# A07_BUS_CONTROL.net
KiCad netlist of a schematic drawn in Altium Designer
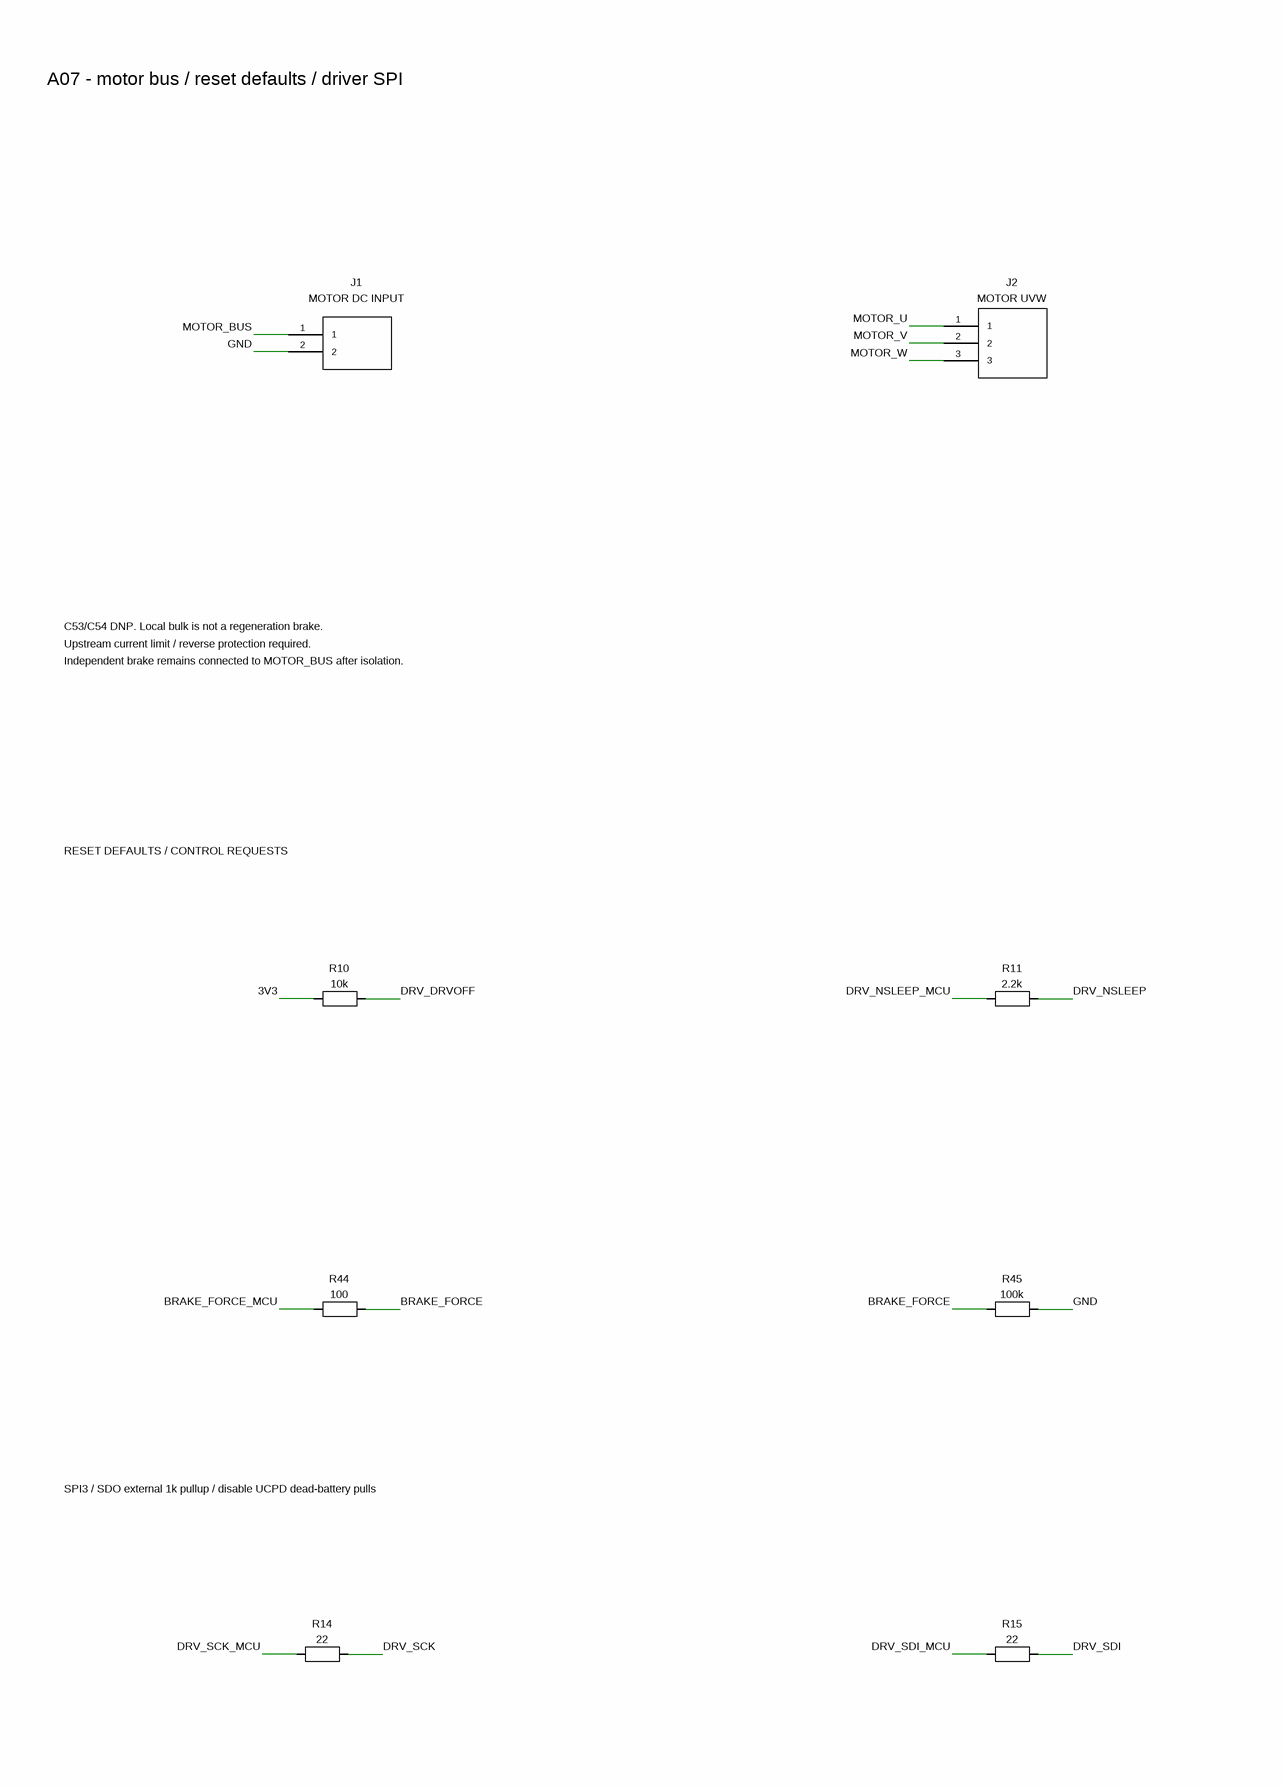
[diagram p0: A07_BUS_CONTROL.SchDoc, left]
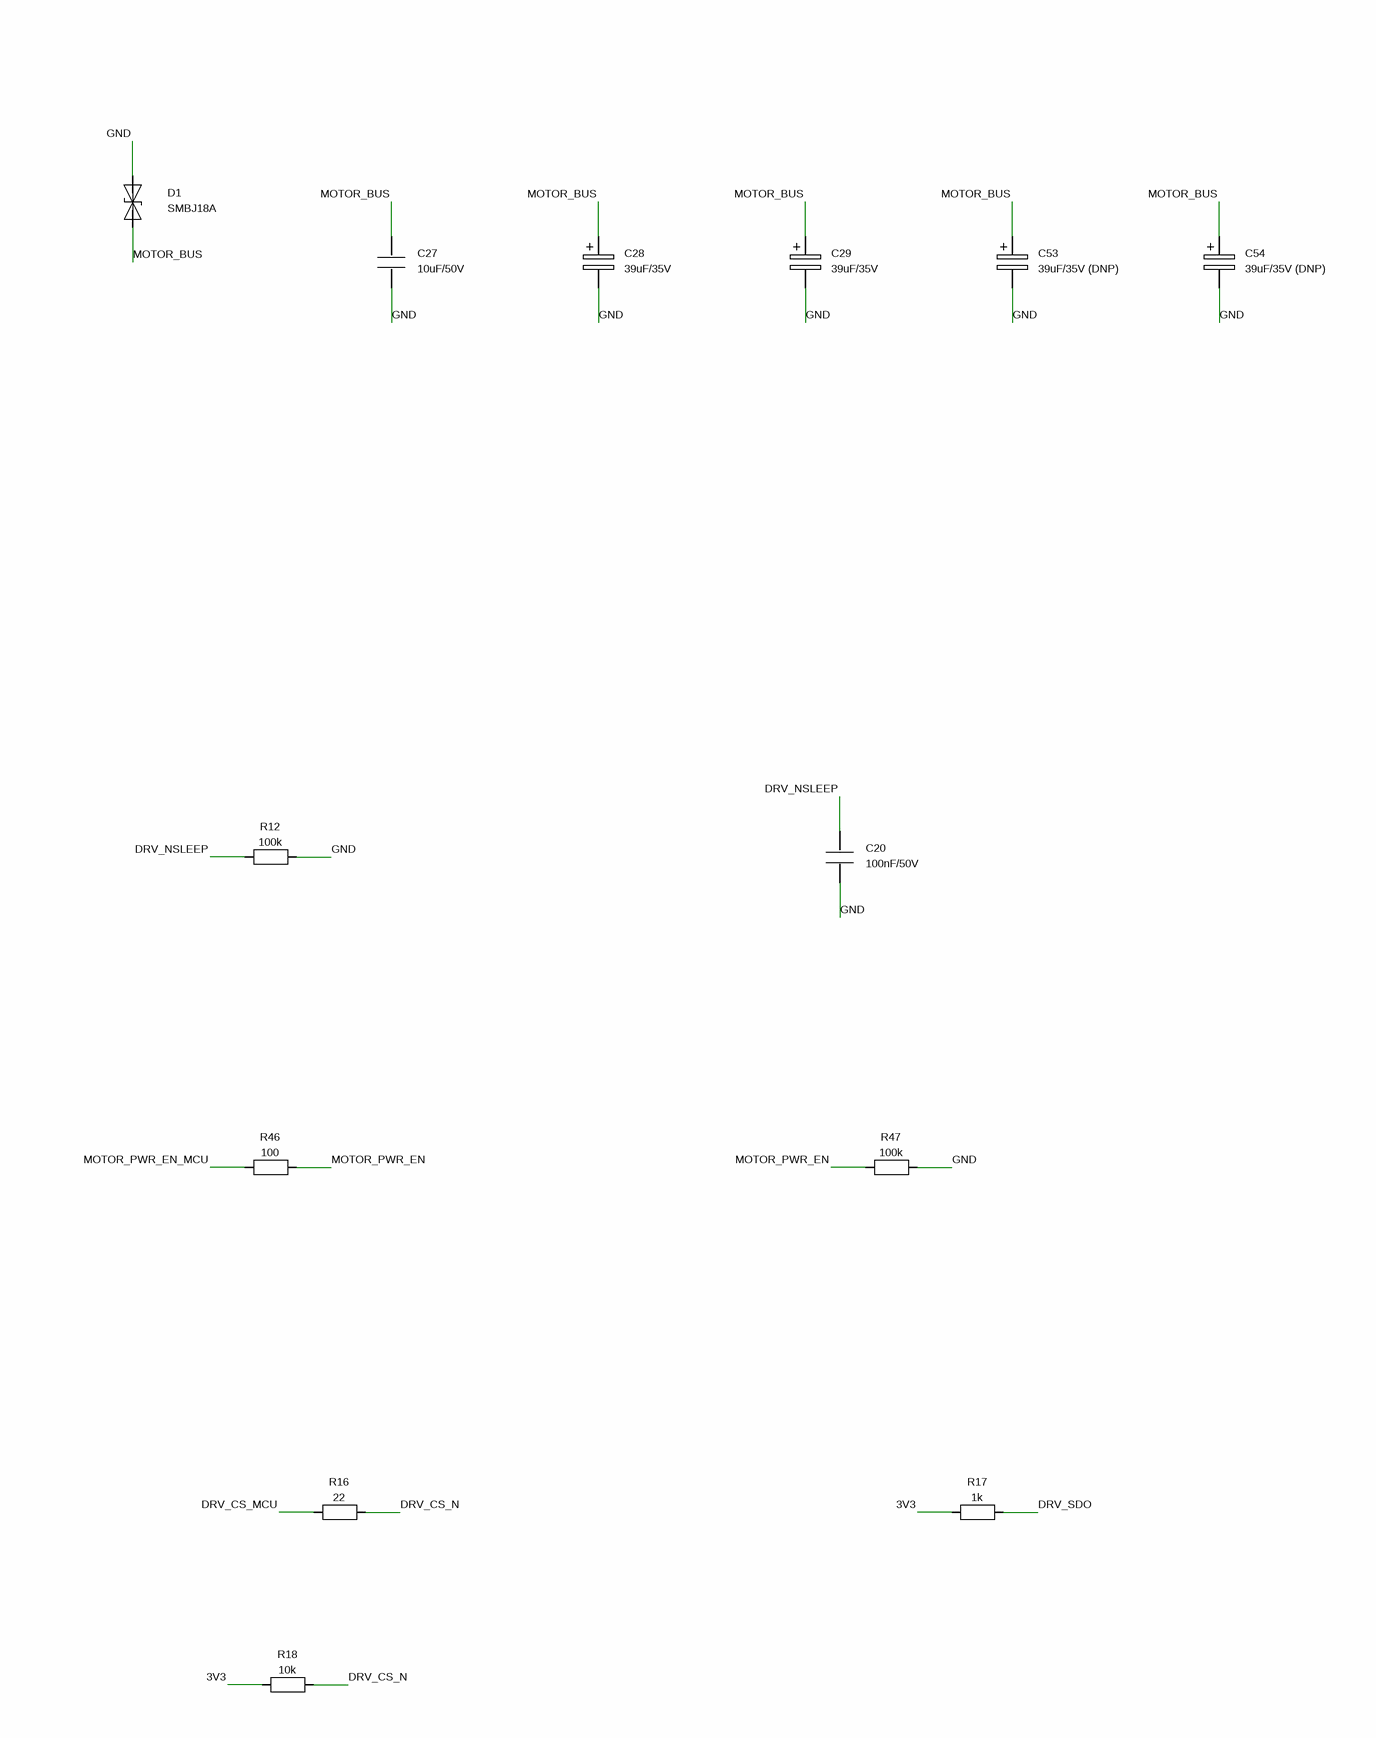
[diagram p1: A07_BUS_CONTROL.SchDoc, right]

(export (version "E")
  (design (tool "Eeschema 10.0.6"))
  (components
    (comp (ref "C20")
      (value "100nF/50V")
      (footprint "User_STM32F407_Ctrl:C0603_M")
      (description "电容")
      (fields (field (name "MPN") "CL10B104KB8NNNC"))
      (libsource (lib "altium-import") (part "root_0_C_"))
    )
    (comp (ref "C27")
      (value "10uF/50V")
      (footprint "User_SamacSys:CAPC3225X270N")
      (description "电容")
      (fields (field (name "MPN") "GRM32ER71H106KA12L"))
      (libsource (lib "altium-import") (part "root_0_C_"))
    )
    (comp (ref "C28")
      (value "39uF/35V")
      (footprint "User_SamacSys:16SVF270M")
      (description "电容")
      (fields (field (name "MPN") "35SVPF39M"))
      (libsource (lib "altium-import") (part "root_0_C_Polarized_"))
    )
    (comp (ref "C29")
      (value "39uF/35V")
      (footprint "User_SamacSys:16SVF270M")
      (description "电容")
      (fields (field (name "MPN") "35SVPF39M"))
      (libsource (lib "altium-import") (part "root_0_C_Polarized_"))
    )
    (comp (ref "C53")
      (value "39uF/35V (DNP)")
      (footprint "User_SamacSys:16SVF270M")
      (description "电容")
      (fields (field (name "MPN") "35SVPF39M"))
      (libsource (lib "altium-import") (part "root_0_C_Polarized_"))
    )
    (comp (ref "C54")
      (value "39uF/35V (DNP)")
      (footprint "User_SamacSys:16SVF270M")
      (description "电容")
      (fields (field (name "MPN") "35SVPF39M"))
      (libsource (lib "altium-import") (part "root_0_C_Polarized_"))
    )
    (comp (ref "D1")
      (value "SMBJ18A")
      (footprint "User_LCSC:C151256_DO-214AA")
      (description "母线瞬态TVS")
      (libsource (lib "altium-import") (part "root_1_D_TVS_"))
    )
    (comp (ref "J1")
      (value "MOTOR DC INPUT")
      (description "电机母线焊线口")
      (fields (field (name "MPN") "2大焊盘+线束应力释放"))
      (libsource (lib "altium-import") (part "root_0_Connector_2_"))
    )
    (comp (ref "J2")
      (value "MOTOR UVW")
      (description "电机三相焊线口")
      (fields (field (name "MPN") "3大焊盘+线束应力释放"))
      (libsource (lib "altium-import") (part "root_0_Connector_3_"))
    )
    (comp (ref "R10")
      (value "10k")
      (footprint "User_STM32F407_Ctrl:R0603_M")
      (description "电阻")
      (fields (field (name "MPN") "通用厚膜 10k 1% 0.1 W"))
      (libsource (lib "altium-import") (part "root_1_R_"))
    )
    (comp (ref "R11")
      (value "2.2k")
      (footprint "User_STM32F407_Ctrl:R0603_M")
      (description "电阻")
      (fields (field (name "MPN") "通用厚膜 2.2k 1% 0.1 W"))
      (libsource (lib "altium-import") (part "root_1_R_"))
    )
    (comp (ref "R12")
      (value "100k")
      (footprint "User_STM32F407_Ctrl:R0603_M")
      (description "电阻")
      (fields (field (name "MPN") "通用厚膜 100k 1% 0.1 W"))
      (libsource (lib "altium-import") (part "root_1_R_"))
    )
    (comp (ref "R14")
      (value "22")
      (footprint "User_STM32F407_Ctrl:R0603_M")
      (description "电阻")
      (fields (field (name "MPN") "通用厚膜 22 1% 0.1 W"))
      (libsource (lib "altium-import") (part "root_1_R_"))
    )
    (comp (ref "R15")
      (value "22")
      (footprint "User_STM32F407_Ctrl:R0603_M")
      (description "电阻")
      (fields (field (name "MPN") "通用厚膜 22 1% 0.1 W"))
      (libsource (lib "altium-import") (part "root_1_R_"))
    )
    (comp (ref "R16")
      (value "22")
      (footprint "User_STM32F407_Ctrl:R0603_M")
      (description "电阻")
      (fields (field (name "MPN") "通用厚膜 22 1% 0.1 W"))
      (libsource (lib "altium-import") (part "root_1_R_"))
    )
    (comp (ref "R17")
      (value "1k")
      (footprint "User_STM32F407_Ctrl:R0603_M")
      (description "电阻")
      (fields (field (name "MPN") "通用厚膜 1k 1% 0.1 W"))
      (libsource (lib "altium-import") (part "root_1_R_"))
    )
    (comp (ref "R18")
      (value "10k")
      (footprint "User_STM32F407_Ctrl:R0603_M")
      (description "电阻")
      (fields (field (name "MPN") "通用厚膜 10k 1% 0.1 W"))
      (libsource (lib "altium-import") (part "root_1_R_"))
    )
    (comp (ref "R44")
      (value "100")
      (footprint "User_STM32F407_Ctrl:R0603_M")
      (description "电阻")
      (fields (field (name "MPN") "通用厚膜 100 1% 0.1 W"))
      (libsource (lib "altium-import") (part "root_1_R_"))
    )
    (comp (ref "R45")
      (value "100k")
      (footprint "User_STM32F407_Ctrl:R0603_M")
      (description "电阻")
      (fields (field (name "MPN") "通用厚膜 100k 1% 0.1 W"))
      (libsource (lib "altium-import") (part "root_1_R_"))
    )
    (comp (ref "R46")
      (value "100")
      (footprint "User_STM32F407_Ctrl:R0603_M")
      (description "电阻")
      (fields (field (name "MPN") "通用厚膜 100 1% 0.1 W"))
      (libsource (lib "altium-import") (part "root_1_R_"))
    )
    (comp (ref "R47")
      (value "100k")
      (footprint "User_STM32F407_Ctrl:R0603_M")
      (description "电阻")
      (fields (field (name "MPN") "通用厚膜 100k 1% 0.1 W"))
      (libsource (lib "altium-import") (part "root_1_R_"))
    )
  )
  (nets
    (net (code "1") (name "/3V3") (class "Default")
      (node (ref "R10") (pin "1") (pintype "passive"))
      (node (ref "R17") (pin "1") (pintype "passive"))
      (node (ref "R18") (pin "1") (pintype "passive"))
    )
    (net (code "2") (name "/BRAKE_FORCE") (class "Default")
      (node (ref "R44") (pin "2") (pintype "passive"))
      (node (ref "R45") (pin "1") (pintype "passive"))
    )
    (net (code "3") (name "/BRAKE_FORCE_MCU") (class "Default")
      (node (ref "R44") (pin "1") (pintype "passive"))
    )
    (net (code "4") (name "/DRV_CS_MCU") (class "Default") (node (ref "R16") (pin "1") (pintype "passive")))
    (net (code "5") (name "/DRV_CS_N") (class "Default")
      (node (ref "R16") (pin "2") (pintype "passive"))
      (node (ref "R18") (pin "2") (pintype "passive"))
    )
    (net (code "6") (name "/DRV_DRVOFF") (class "Default") (node (ref "R10") (pin "2") (pintype "passive")))
    (net (code "7") (name "/DRV_NSLEEP") (class "Default")
      (node (ref "C20") (pin "1") (pintype "passive"))
      (node (ref "R11") (pin "2") (pintype "passive"))
      (node (ref "R12") (pin "1") (pintype "passive"))
    )
    (net (code "8") (name "/DRV_NSLEEP_MCU") (class "Default")
      (node (ref "R11") (pin "1") (pintype "passive"))
    )
    (net (code "9") (name "/DRV_SCK") (class "Default") (node (ref "R14") (pin "2") (pintype "passive")))
    (net (code "10") (name "/DRV_SCK_MCU") (class "Default") (node (ref "R14") (pin "1") (pintype "passive")))
    (net (code "11") (name "/DRV_SDI") (class "Default") (node (ref "R15") (pin "2") (pintype "passive")))
    (net (code "12") (name "/DRV_SDI_MCU") (class "Default") (node (ref "R15") (pin "1") (pintype "passive")))
    (net (code "13") (name "/DRV_SDO") (class "Default") (node (ref "R17") (pin "2") (pintype "passive")))
    (net (code "14") (name "/GND") (class "Default")
      (node (ref "C20") (pin "2") (pintype "passive"))
      (node (ref "C27") (pin "2") (pintype "passive"))
      (node (ref "C28") (pin "2") (pintype "passive"))
      (node (ref "C29") (pin "2") (pintype "passive"))
      (node (ref "C53") (pin "2") (pintype "passive"))
      (node (ref "C54") (pin "2") (pintype "passive"))
      (node (ref "D1") (pin "2") (pinfunction "A2_2") (pintype "passive"))
      (node (ref "J1") (pin "2") (pinfunction "2_2") (pintype "passive"))
      (node (ref "R12") (pin "2") (pintype "passive"))
      (node (ref "R45") (pin "2") (pintype "passive"))
      (node (ref "R47") (pin "2") (pintype "passive"))
    )
    (net (code "15") (name "/MOTOR_BUS") (class "Default")
      (node (ref "C27") (pin "1") (pintype "passive"))
      (node (ref "C28") (pin "1") (pintype "passive"))
      (node (ref "C29") (pin "1") (pintype "passive"))
      (node (ref "C53") (pin "1") (pintype "passive"))
      (node (ref "C54") (pin "1") (pintype "passive"))
      (node (ref "D1") (pin "1") (pinfunction "A1_1") (pintype "passive"))
      (node (ref "J1") (pin "1") (pinfunction "1_1") (pintype "passive"))
    )
    (net (code "16") (name "/MOTOR_PWR_EN") (class "Default")
      (node (ref "R46") (pin "2") (pintype "passive"))
      (node (ref "R47") (pin "1") (pintype "passive"))
    )
    (net (code "17") (name "/MOTOR_PWR_EN_MCU") (class "Default")
      (node (ref "R46") (pin "1") (pintype "passive"))
    )
    (net (code "18") (name "/MOTOR_U") (class "Default")
      (node (ref "J2") (pin "1") (pinfunction "1_1") (pintype "passive"))
    )
    (net (code "19") (name "/MOTOR_V") (class "Default")
      (node (ref "J2") (pin "2") (pinfunction "2_2") (pintype "passive"))
    )
    (net (code "20") (name "/MOTOR_W") (class "Default")
      (node (ref "J2") (pin "3") (pinfunction "3_3") (pintype "passive"))
    )
  )
)
